# Slave_CA.net
KiCad netlist of a schematic drawn in Altium Designer
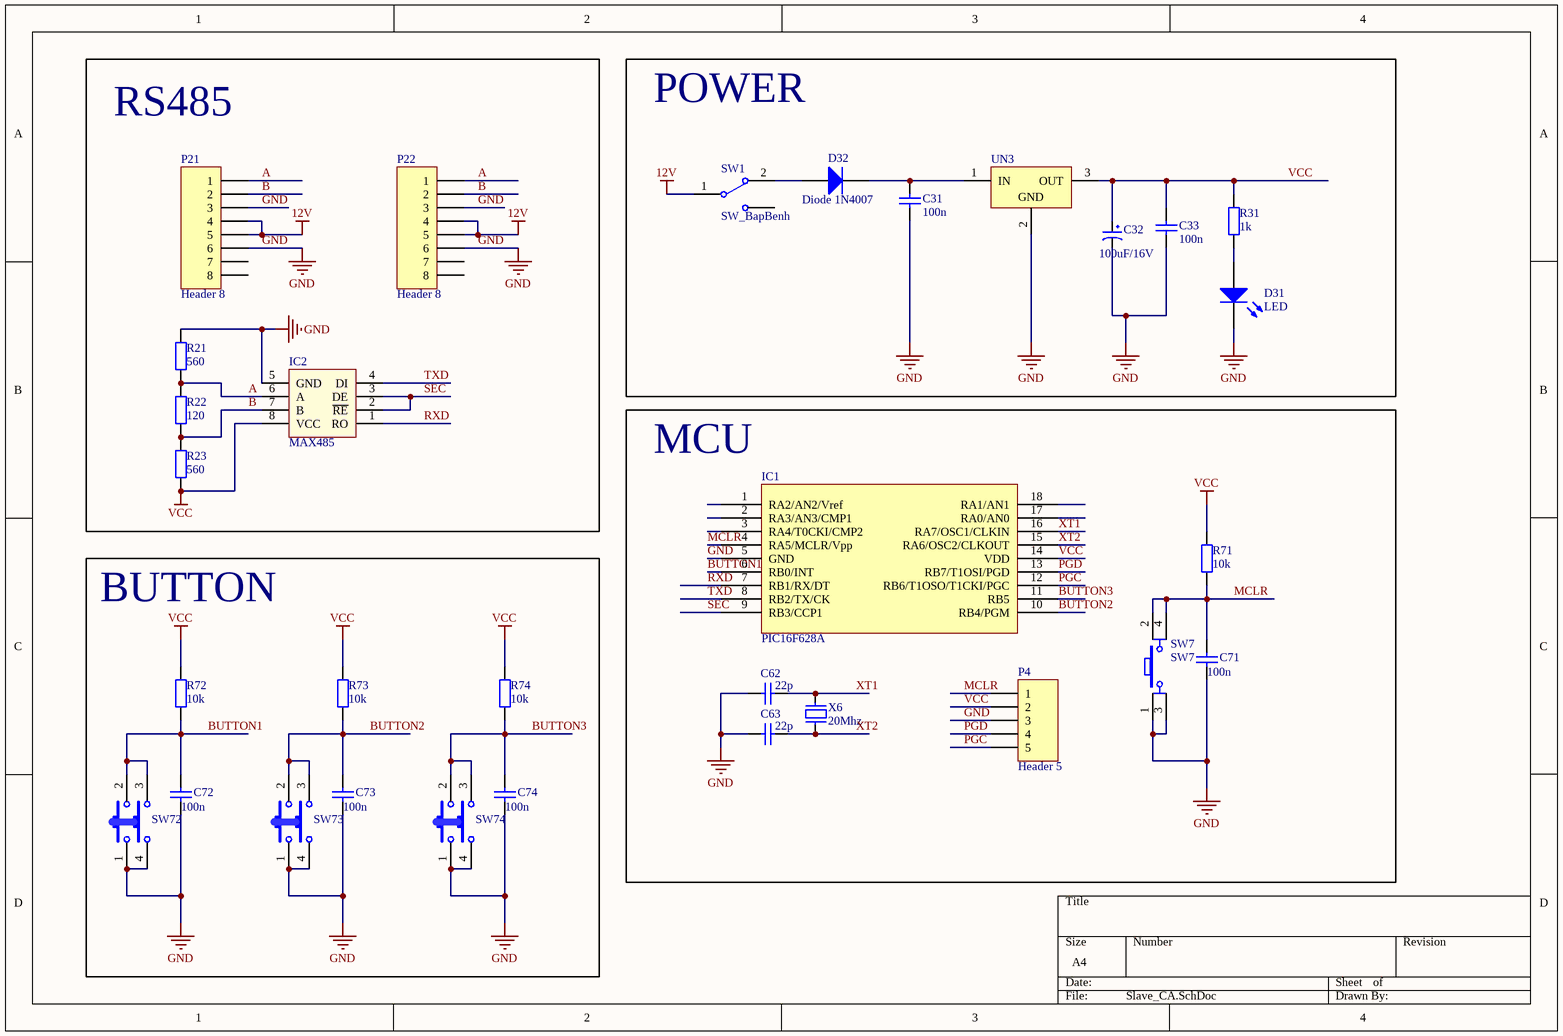
[diagram p0: Slave_CA.SchDoc]

(export (version "E")
  (design (tool "Eeschema 10.0.6"))
  (components
    (comp (ref "C31")
      (value "100n")
      (footprint "C-NP-0805")
      (description "Non-polarized Capacitor")
      (fields (field (name "Comment") "Cap Non-pol") (field (name "PUBLISHER") "Altium Limited"))
      (libsource (lib "THG") (part "Cap Non-pol"))
    )
    (comp (ref "C32")
      (value "100uF/16V")
      (footprint "CP1.5/3.4")
      (description "Cap 100uF/35V - 470uF/16V")
      (libsource (lib "syhaunguyen") (part "CP3"))
    )
    (comp (ref "C33")
      (value "100n")
      (footprint "C-NP-0805")
      (description "Non-polarized Capacitor")
      (fields (field (name "Comment") "Cap Non-pol") (field (name "PUBLISHER") "Altium Limited"))
      (libsource (lib "THG") (part "Cap Non-pol"))
    )
    (comp (ref "C62")
      (value "22p")
      (footprint "C-NP-0805")
      (description "Non-polarized Capacitor")
      (fields (field (name "Comment") "Cap Non-pol") (field (name "PUBLISHER") "Altium Limited"))
      (libsource (lib "THG") (part "Cap Non-pol"))
    )
    (comp (ref "C63")
      (value "22p")
      (footprint "C-NP-0805")
      (description "Non-polarized Capacitor")
      (fields (field (name "Comment") "Cap Non-pol") (field (name "PUBLISHER") "Altium Limited"))
      (libsource (lib "THG") (part "Cap Non-pol"))
    )
    (comp (ref "C71")
      (value "100n")
      (footprint "CAP_SMD_0805")
      (description "Capacitor")
      (fields (field (name "Comment") "Capacitor Ceramic") (field (name "PUBLISHER") "Altium Limited"))
      (libsource (lib "THG") (part "CapSMD"))
    )
    (comp (ref "C72")
      (value "100n")
      (footprint "CAP_SMD_0805")
      (description "Capacitor")
      (fields (field (name "Comment") "Capacitor Ceramic") (field (name "PUBLISHER") "Altium Limited"))
      (libsource (lib "THG") (part "CapSMD"))
    )
    (comp (ref "C73")
      (value "100n")
      (footprint "CAP_SMD_0805")
      (description "Capacitor")
      (fields (field (name "Comment") "Capacitor Ceramic") (field (name "PUBLISHER") "Altium Limited"))
      (libsource (lib "THG") (part "CapSMD"))
    )
    (comp (ref "C74")
      (value "100n")
      (footprint "CAP_SMD_0805")
      (description "Capacitor")
      (fields (field (name "Comment") "Capacitor Ceramic") (field (name "PUBLISHER") "Altium Limited"))
      (libsource (lib "THG") (part "CapSMD"))
    )
    (comp (ref "D31")
      (value "LED")
      (footprint "LED-0805 RED")
      (description "Typical LED")
      (fields (field (name "PUBLISHER") "Altium Limited"))
      (libsource (lib "THG") (part "LED"))
    )
    (comp (ref "D32")
      (value "Diode 1N4007")
      (footprint "DO-41")
      (description "1 Amp General Purpose Rectifier")
      (fields (field (name "PUBLISHER") "Altium Limited"))
      (libsource (lib "hphonglib") (part "Diode 1N4007"))
    )
    (comp (ref "IC1")
      (value "PIC16F628A")
      (footprint "DIP18/W0.3")
      (libsource (lib "THG") (part "PIC16F628A"))
    )
    (comp (ref "IC2")
      (value "MAX485")
      (footprint "DIP8/W0.3")
      (description "RS232 - RS485 (Same sn75176)")
      (libsource (lib "syhaunguyen") (part "MAX485"))
    )
    (comp (ref "P4")
      (value "Header 5")
      (footprint "Header 5")
      (description "Header, 5-Pin")
      (fields (field (name "PUBLISHER") "Altium Limited"))
      (libsource (lib "THG") (part "Header 5"))
    )
    (comp (ref "P21")
      (value "Header 8")
      (footprint "RJ11")
      (description "Header, 8-Pin")
      (fields (field (name "PUBLISHER") "Altium Limited"))
      (libsource (lib "THG") (part "Header 8"))
    )
    (comp (ref "P22")
      (value "Header 8")
      (footprint "RJ11")
      (description "Header, 8-Pin")
      (fields (field (name "PUBLISHER") "Altium Limited"))
      (libsource (lib "THG") (part "Header 8"))
    )
    (comp (ref "R21")
      (value "560")
      (footprint "DIEN TRO 0805")
      (description "RES_0805")
      (fields (field (name "Comment") "RES_SMD_0805") (field (name "PUBLISHER") "Altium Limited"))
      (libsource (lib "THG") (part "RES_SMD_0805"))
    )
    (comp (ref "R22")
      (value "120")
      (footprint "DIEN TRO 0805")
      (description "RES_0805")
      (fields (field (name "Comment") "RES_SMD_0805") (field (name "PUBLISHER") "Altium Limited"))
      (libsource (lib "THG") (part "RES_SMD_0805"))
    )
    (comp (ref "R23")
      (value "560")
      (footprint "DIEN TRO 0805")
      (description "RES_0805")
      (fields (field (name "Comment") "RES_SMD_0805") (field (name "PUBLISHER") "Altium Limited"))
      (libsource (lib "THG") (part "RES_SMD_0805"))
    )
    (comp (ref "R31")
      (value "1k")
      (footprint "DIEN TRO 0805")
      (description "RES_0805")
      (fields (field (name "Comment") "RES_SMD_0805") (field (name "PUBLISHER") "Altium Limited"))
      (libsource (lib "THG") (part "RES_SMD_0805"))
    )
    (comp (ref "R71")
      (value "10k")
      (footprint "DIEN TRO 0805")
      (description "RES_0805")
      (fields (field (name "Comment") "RES_SMD_0805") (field (name "PUBLISHER") "Altium Limited"))
      (libsource (lib "THG") (part "RES_SMD_0805"))
    )
    (comp (ref "R72")
      (value "10k")
      (footprint "DIEN TRO 0805")
      (description "RES_0805")
      (fields (field (name "Comment") "RES_SMD_0805") (field (name "PUBLISHER") "Altium Limited"))
      (libsource (lib "THG") (part "RES_SMD_0805"))
    )
    (comp (ref "R73")
      (value "10k")
      (footprint "DIEN TRO 0805")
      (description "RES_0805")
      (fields (field (name "Comment") "RES_SMD_0805") (field (name "PUBLISHER") "Altium Limited"))
      (libsource (lib "THG") (part "RES_SMD_0805"))
    )
    (comp (ref "R74")
      (value "10k")
      (footprint "DIEN TRO 0805")
      (description "RES_0805")
      (fields (field (name "Comment") "RES_SMD_0805") (field (name "PUBLISHER") "Altium Limited"))
      (libsource (lib "THG") (part "RES_SMD_0805"))
    )
    (comp (ref "SW1")
      (value "SW_BapBenh")
      (footprint "SW_Bapbenh")
      (libsource (lib "THG") (part "SW_BapBenh"))
    )
    (comp (ref "SW7")
      (value "SW7")
      (footprint "SW4")
      (description "Switch button 4 pin")
      (libsource (lib "syhaunguyen") (part "SW4"))
    )
    (comp (ref "SW72")
      (value "SW-4P-B")
      (footprint "SW-4P-B")
      (description "Switch Big 4 Pin")
      (fields (field (name "PUBLISHER") "Altium Limited"))
      (libsource (lib "hphonglib") (part "SW-4PIN-BIG"))
    )
    (comp (ref "SW73")
      (value "SW-4P-B")
      (footprint "SW-4P-B")
      (description "Switch Big 4 Pin")
      (fields (field (name "PUBLISHER") "Altium Limited"))
      (libsource (lib "hphonglib") (part "SW-4PIN-BIG"))
    )
    (comp (ref "SW74")
      (value "SW-4P-B")
      (footprint "SW-4P-B")
      (description "Switch Big 4 Pin")
      (fields (field (name "PUBLISHER") "Altium Limited"))
      (libsource (lib "hphonglib") (part "SW-4PIN-BIG"))
    )
    (comp (ref "UN3")
      (value "L78M05CP")
      (footprint "QTO-220")
      (description "Positive Voltage Regulator")
      (fields (field (name "PUBLISHER") "Altium Limited"))
      (libsource (lib "syhaunguyen") (part "L78M05CP"))
    )
    (comp (ref "X6")
      (value "20Mhz")
      (footprint "XT2")
      (description "Crystal For all Crystal 2pin.")
      (libsource (lib "syhaunguyen") (part "XT2"))
    )
  )
  (nets
    (net (code "1") (name "/A") (class "Default")
      (node (ref "IC2") (pin "6") (pinfunction "A_6") (pintype "passive"))
      (node (ref "P21") (pin "1") (pinfunction "1_1") (pintype "passive"))
      (node (ref "P22") (pin "1") (pinfunction "1_1") (pintype "passive"))
      (node (ref "R21") (pin "1") (pinfunction "1_1") (pintype "passive"))
      (node (ref "R22") (pin "2") (pinfunction "2_2") (pintype "passive"))
    )
    (net (code "2") (name "/B") (class "Default")
      (node (ref "IC2") (pin "7") (pinfunction "B_7") (pintype "passive"))
      (node (ref "P21") (pin "2") (pinfunction "2_2") (pintype "passive"))
      (node (ref "P22") (pin "2") (pinfunction "2_2") (pintype "passive"))
      (node (ref "R22") (pin "1") (pinfunction "1_1") (pintype "passive"))
      (node (ref "R23") (pin "2") (pinfunction "2_2") (pintype "passive"))
    )
    (net (code "3") (name "/BUTTON1") (class "Default")
      (node (ref "C72") (pin "2") (pinfunction "2_2") (pintype "passive"))
      (node (ref "IC1") (pin "6") (pinfunction "RB0/INT_6") (pintype "passive"))
      (node (ref "R72") (pin "1") (pinfunction "1_1") (pintype "passive"))
      (node (ref "SW72") (pin "2") (pinfunction "2_2") (pintype "passive"))
      (node (ref "SW72") (pin "3") (pinfunction "3_3") (pintype "passive"))
    )
    (net (code "4") (name "/BUTTON2") (class "Default")
      (node (ref "C73") (pin "2") (pinfunction "2_2") (pintype "passive"))
      (node (ref "IC1") (pin "10") (pinfunction "RB4/PGM_10") (pintype "passive"))
      (node (ref "R73") (pin "1") (pinfunction "1_1") (pintype "passive"))
      (node (ref "SW73") (pin "2") (pinfunction "2_2") (pintype "passive"))
      (node (ref "SW73") (pin "3") (pinfunction "3_3") (pintype "passive"))
    )
    (net (code "5") (name "/BUTTON3") (class "Default")
      (node (ref "C74") (pin "2") (pinfunction "2_2") (pintype "passive"))
      (node (ref "IC1") (pin "11") (pinfunction "RB5_11") (pintype "passive"))
      (node (ref "R74") (pin "1") (pinfunction "1_1") (pintype "passive"))
      (node (ref "SW74") (pin "2") (pinfunction "2_2") (pintype "passive"))
      (node (ref "SW74") (pin "3") (pinfunction "3_3") (pintype "passive"))
    )
    (net (code "6") (name "/MCLR") (class "Default")
      (node (ref "C71") (pin "2") (pinfunction "2_2") (pintype "passive"))
      (node (ref "IC1") (pin "4") (pinfunction "RA5/MCLR/Vpp_4") (pintype "passive"))
      (node (ref "P4") (pin "1") (pinfunction "1_1") (pintype "passive"))
      (node (ref "R71") (pin "1") (pinfunction "1_1") (pintype "passive"))
      (node (ref "SW7") (pin "2") (pintype "passive"))
      (node (ref "SW7") (pin "4") (pintype "passive"))
    )
    (net (code "7") (name "/PGC") (class "Default")
      (node (ref "IC1") (pin "12") (pinfunction "RB6/T1OSO/T1CKI/PGC_12") (pintype "passive"))
      (node (ref "P4") (pin "5") (pinfunction "5_5") (pintype "passive"))
    )
    (net (code "8") (name "/PGD") (class "Default")
      (node (ref "IC1") (pin "13") (pinfunction "RB7/T1OSI/PGD_13") (pintype "passive"))
      (node (ref "P4") (pin "4") (pinfunction "4_4") (pintype "passive"))
    )
    (net (code "9") (name "/RXD") (class "Default")
      (node (ref "IC1") (pin "7") (pinfunction "RB1/RX/DT_7") (pintype "passive"))
      (node (ref "IC2") (pin "1") (pinfunction "RO_1") (pintype "passive"))
    )
    (net (code "10") (name "/SEC") (class "Default")
      (node (ref "IC1") (pin "9") (pinfunction "RB3/CCP1_9") (pintype "passive"))
      (node (ref "IC2") (pin "2") (pinfunction "~{RE}_2") (pintype "passive"))
      (node (ref "IC2") (pin "3") (pinfunction "DE_3") (pintype "passive"))
    )
    (net (code "11") (name "/TXD") (class "Default")
      (node (ref "IC1") (pin "8") (pinfunction "RB2/TX/CK_8") (pintype "passive"))
      (node (ref "IC2") (pin "4") (pinfunction "DI_4") (pintype "passive"))
    )
    (net (code "12") (name "/XT1") (class "Default")
      (node (ref "C62") (pin "1") (pinfunction "1_1") (pintype "passive"))
      (node (ref "IC1") (pin "16") (pinfunction "RA7/OSC1/CLKIN_16") (pintype "passive"))
      (node (ref "X6") (pin "2") (pinfunction "2_2") (pintype "passive"))
    )
    (net (code "13") (name "/XT2") (class "Default")
      (node (ref "C63") (pin "1") (pinfunction "1_1") (pintype "passive"))
      (node (ref "IC1") (pin "15") (pinfunction "RA6/OSC2/CLKOUT_15") (pintype "passive"))
      (node (ref "X6") (pin "1") (pinfunction "1_1") (pintype "passive"))
    )
    (net (code "14") (name "12V") (class "Default")
      (node (ref "P21") (pin "4") (pinfunction "4_4") (pintype "passive"))
      (node (ref "P21") (pin "5") (pinfunction "5_5") (pintype "passive"))
      (node (ref "P22") (pin "4") (pinfunction "4_4") (pintype "passive"))
      (node (ref "P22") (pin "5") (pinfunction "5_5") (pintype "passive"))
      (node (ref "SW1") (pin "1") (pinfunction "1_1") (pintype "passive"))
    )
    (net (code "15") (name "GND") (class "Default")
      (node (ref "C31") (pin "1") (pinfunction "1_1") (pintype "passive"))
      (node (ref "C32") (pin "2") (pinfunction "2_2") (pintype "passive"))
      (node (ref "C33") (pin "1") (pinfunction "1_1") (pintype "passive"))
      (node (ref "C62") (pin "2") (pinfunction "2_2") (pintype "passive"))
      (node (ref "C63") (pin "2") (pinfunction "2_2") (pintype "passive"))
      (node (ref "C71") (pin "1") (pinfunction "1_1") (pintype "passive"))
      (node (ref "C72") (pin "1") (pinfunction "1_1") (pintype "passive"))
      (node (ref "C73") (pin "1") (pinfunction "1_1") (pintype "passive"))
      (node (ref "C74") (pin "1") (pinfunction "1_1") (pintype "passive"))
      (node (ref "D31") (pin "2") (pinfunction "K_2") (pintype "passive"))
      (node (ref "IC1") (pin "5") (pinfunction "GND_5") (pintype "passive"))
      (node (ref "IC2") (pin "5") (pinfunction "GND_5") (pintype "passive"))
      (node (ref "P21") (pin "3") (pinfunction "3_3") (pintype "passive"))
      (node (ref "P21") (pin "6") (pinfunction "6_6") (pintype "passive"))
      (node (ref "P22") (pin "3") (pinfunction "3_3") (pintype "passive"))
      (node (ref "P22") (pin "6") (pinfunction "6_6") (pintype "passive"))
      (node (ref "P4") (pin "3") (pinfunction "3_3") (pintype "passive"))
      (node (ref "R21") (pin "2") (pinfunction "2_2") (pintype "passive"))
      (node (ref "SW7") (pin "1") (pintype "passive"))
      (node (ref "SW7") (pin "3") (pintype "passive"))
      (node (ref "SW72") (pin "1") (pinfunction "1_1") (pintype "passive"))
      (node (ref "SW72") (pin "4") (pinfunction "4_4") (pintype "passive"))
      (node (ref "SW73") (pin "1") (pinfunction "1_1") (pintype "passive"))
      (node (ref "SW73") (pin "4") (pinfunction "4_4") (pintype "passive"))
      (node (ref "SW74") (pin "1") (pinfunction "1_1") (pintype "passive"))
      (node (ref "SW74") (pin "4") (pinfunction "4_4") (pintype "passive"))
      (node (ref "UN3") (pin "2") (pinfunction "GND_2") (pintype "power_in"))
    )
    (net (code "16") (name "Net-(D31-A)") (class "Default")
      (node (ref "D31") (pin "1") (pinfunction "A_1") (pintype "passive"))
      (node (ref "R31") (pin "1") (pinfunction "1_1") (pintype "passive"))
    )
    (net (code "17") (name "Net-(D32-A)") (class "Default")
      (node (ref "D32") (pin "1") (pinfunction "A_1") (pintype "passive"))
      (node (ref "SW1") (pin "2") (pinfunction "2_2") (pintype "passive"))
    )
    (net (code "18") (name "Net-(D32-K)") (class "Default")
      (node (ref "C31") (pin "2") (pinfunction "2_2") (pintype "passive"))
      (node (ref "D32") (pin "2") (pinfunction "K_2") (pintype "passive"))
      (node (ref "UN3") (pin "1") (pinfunction "IN_1") (pintype "power_in"))
    )
    (net (code "19") (name "VCC") (class "Default")
      (node (ref "C32") (pin "1") (pinfunction "1_1") (pintype "passive"))
      (node (ref "C33") (pin "2") (pinfunction "2_2") (pintype "passive"))
      (node (ref "IC1") (pin "14") (pinfunction "VDD_14") (pintype "passive"))
      (node (ref "IC2") (pin "8") (pinfunction "VCC_8") (pintype "passive"))
      (node (ref "P4") (pin "2") (pinfunction "2_2") (pintype "passive"))
      (node (ref "R23") (pin "1") (pinfunction "1_1") (pintype "passive"))
      (node (ref "R31") (pin "2") (pinfunction "2_2") (pintype "passive"))
      (node (ref "R71") (pin "2") (pinfunction "2_2") (pintype "passive"))
      (node (ref "R72") (pin "2") (pinfunction "2_2") (pintype "passive"))
      (node (ref "R73") (pin "2") (pinfunction "2_2") (pintype "passive"))
      (node (ref "R74") (pin "2") (pinfunction "2_2") (pintype "passive"))
      (node (ref "UN3") (pin "3") (pinfunction "OUT_3") (pintype "power_in"))
    )
    (net (code "20") (name "unconnected-(IC1-RA0{slash}AN0-Pad17)") (class "Default")
      (node (ref "IC1") (pin "17") (pinfunction "RA0/AN0_17") (pintype "passive"))
    )
    (net (code "21") (name "unconnected-(IC1-RA1{slash}AN1-Pad18)") (class "Default")
      (node (ref "IC1") (pin "18") (pinfunction "RA1/AN1_18") (pintype "passive"))
    )
    (net (code "22") (name "unconnected-(IC1-RA2{slash}AN2{slash}Vref-Pad1)") (class "Default")
      (node (ref "IC1") (pin "1") (pinfunction "RA2/AN2/Vref_1") (pintype "passive"))
    )
    (net (code "23") (name "unconnected-(IC1-RA3{slash}AN3{slash}CMP1-Pad2)") (class "Default")
      (node (ref "IC1") (pin "2") (pinfunction "RA3/AN3/CMP1_2") (pintype "passive"))
    )
    (net (code "24") (name "unconnected-(IC1-RA4{slash}T0CKI{slash}CMP2-Pad3)") (class "Default")
      (node (ref "IC1") (pin "3") (pinfunction "RA4/T0CKI/CMP2_3") (pintype "passive"))
    )
    (net (code "25") (name "unconnected-(P21-Pad7)") (class "Default")
      (node (ref "P21") (pin "7") (pinfunction "7_7") (pintype "passive"))
    )
    (net (code "26") (name "unconnected-(P21-Pad8)") (class "Default")
      (node (ref "P21") (pin "8") (pinfunction "8_8") (pintype "passive"))
    )
    (net (code "27") (name "unconnected-(P22-Pad7)") (class "Default")
      (node (ref "P22") (pin "7") (pinfunction "7_7") (pintype "passive"))
    )
    (net (code "28") (name "unconnected-(P22-Pad8)") (class "Default")
      (node (ref "P22") (pin "8") (pinfunction "8_8") (pintype "passive"))
    )
  )
)
